# POWER.net
KiCad netlist of a schematic drawn in Altium Designer
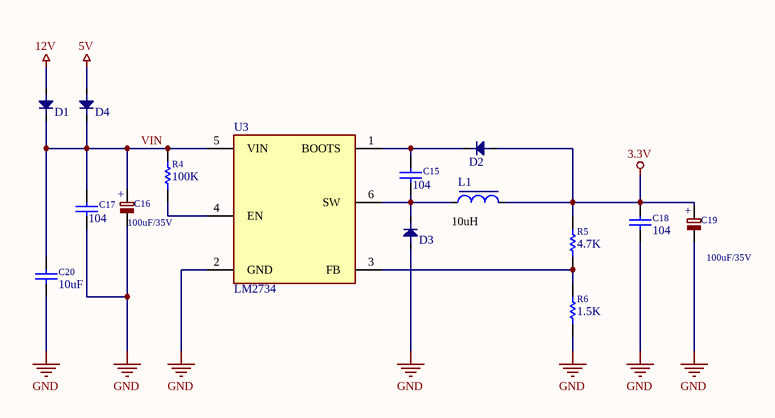
[diagram p0: POWER.SchDoc]

(export (version "E")
  (design (tool "Eeschema 10.0.6"))
  (components
    (comp (ref "C15")
      (value "104")
      (footprint "C2012-0805")
      (description "Capacitor")
      (fields (field (name "PUBLISHER") "Hoang Nguyen"))
      (libsource (lib "VPMyLibrary") (part "Cap {lt}SMD{gt}"))
    )
    (comp (ref "C16")
      (value "100uF/35V")
      (footprint "CAP_100/35V")
      (description "Polarized Capacitor")
      (fields (field (name "MANUFACTURER") "FARNELL") (field (name "PUBLISHER") "Hoang Nguyen"))
      (libsource (lib "VPMyLibrary") (part "Cap_Pol {lt}DIP{gt}"))
    )
    (comp (ref "C17")
      (value "104")
      (footprint "C2012-0805")
      (description "Capacitor")
      (fields (field (name "PUBLISHER") "Hoang Nguyen"))
      (libsource (lib "VPMyLibrary") (part "Cap {lt}SMD{gt}"))
    )
    (comp (ref "C18")
      (value "104")
      (footprint "C2012-0805")
      (description "Capacitor")
      (fields (field (name "PUBLISHER") "Hoang Nguyen"))
      (libsource (lib "VPMyLibrary") (part "Cap {lt}SMD{gt}"))
    )
    (comp (ref "C19")
      (value "100uF/35V")
      (footprint "CAP_100/35V")
      (description "Polarized Capacitor")
      (fields (field (name "MANUFACTURER") "FARNELL") (field (name "PUBLISHER") "Hoang Nguyen"))
      (libsource (lib "VPMyLibrary") (part "Cap_Pol {lt}DIP{gt}"))
    )
    (comp (ref "C20")
      (value "10uF")
      (footprint "C1210")
      (description "Capacitor")
      (fields (field (name "PUBLISHER") "Hoang Nguyen"))
      (libsource (lib "VPMyLibrary") (part "Cap {lt}SMD{gt}"))
    )
    (comp (ref "D1")
      (value "SS34")
      (footprint "DO-214AC,SMA")
      (fields (field (name "PUBLISHER") "Altium Limited"))
      (libsource (lib "VPMyLibrary") (part "Didode_Smd"))
    )
    (comp (ref "D2")
      (value "SS34")
      (footprint "DO-214AC,SMA")
      (fields (field (name "PUBLISHER") "Altium Limited"))
      (libsource (lib "VPMyLibrary") (part "Didode_Smd"))
    )
    (comp (ref "D3")
      (value "SS34")
      (footprint "DO-214AC,SMA")
      (fields (field (name "PUBLISHER") "Altium Limited"))
      (libsource (lib "VPMyLibrary") (part "Didode_Smd"))
    )
    (comp (ref "D4")
      (value "SS34")
      (footprint "DO-214AC,SMA")
      (fields (field (name "PUBLISHER") "Altium Limited"))
      (libsource (lib "VPMyLibrary") (part "Didode_Smd"))
    )
    (comp (ref "L1")
      (value "10uH")
      (footprint "L-6030")
      (description "Smd Inductors")
      (fields (field (name "PUBLISHER") "Altium Limited"))
      (libsource (lib "VPMyLibrary") (part "Inductor Ferrite"))
    )
    (comp (ref "R4")
      (value "100K")
      (footprint "R2012-0805")
      (description "Resistor")
      (fields (field (name "Comment") "4.7K") (field (name "PUBLISHER") "Hoang Nguyen"))
      (libsource (lib "VPMyLibrary") (part "Resistor {lt}SMD{gt}"))
    )
    (comp (ref "R5")
      (value "4.7K")
      (footprint "R2012-0805")
      (description "Resistor")
      (fields (field (name "PUBLISHER") "Hoang Nguyen"))
      (libsource (lib "VPMyLibrary") (part "Resistor {lt}SMD{gt}"))
    )
    (comp (ref "R6")
      (value "1.5K")
      (footprint "R2012-0805")
      (description "Resistor")
      (fields (field (name "PUBLISHER") "Hoang Nguyen"))
      (libsource (lib "VPMyLibrary") (part "Resistor {lt}SMD{gt}"))
    )
    (comp (ref "U3")
      (value "LM2734")
      (footprint "SOT23-6")
      (description "Step-Down DC-DC Regulator")
      (libsource (lib "VPMyLibrary") (part "LM2734"))
    )
  )
  (nets
    (net (code "1") (name "/VIN") (class "Default")
      (node (ref "C16") (pin "1") (pinfunction "+_1") (pintype "passive"))
      (node (ref "C17") (pin "1") (pinfunction "1_1") (pintype "passive"))
      (node (ref "C20") (pin "1") (pinfunction "1_1") (pintype "passive"))
      (node (ref "D1") (pin "2") (pinfunction "K_2") (pintype "passive"))
      (node (ref "D4") (pin "2") (pinfunction "K_2") (pintype "passive"))
      (node (ref "R4") (pin "2") (pinfunction "2_2") (pintype "passive"))
      (node (ref "U3") (pin "5") (pinfunction "VIN_5") (pintype "passive"))
    )
    (net (code "2") (name "3.3V") (class "Default")
      (node (ref "C18") (pin "1") (pinfunction "1_1") (pintype "passive"))
      (node (ref "C19") (pin "1") (pinfunction "+_1") (pintype "passive"))
      (node (ref "D2") (pin "1") (pinfunction "A_1") (pintype "passive"))
      (node (ref "L1") (pin "2") (pinfunction "2_2") (pintype "passive"))
      (node (ref "R5") (pin "2") (pinfunction "2_2") (pintype "passive"))
    )
    (net (code "3") (name "5V") (class "Default")
      (node (ref "D4") (pin "1") (pinfunction "A_1") (pintype "passive"))
    )
    (net (code "4") (name "12V") (class "Default")
      (node (ref "D1") (pin "1") (pinfunction "A_1") (pintype "passive"))
    )
    (net (code "5") (name "GND") (class "Default")
      (node (ref "C16") (pin "2") (pinfunction "-_2") (pintype "passive"))
      (node (ref "C17") (pin "2") (pinfunction "2_2") (pintype "passive"))
      (node (ref "C18") (pin "2") (pinfunction "2_2") (pintype "passive"))
      (node (ref "C19") (pin "2") (pinfunction "-_2") (pintype "passive"))
      (node (ref "C20") (pin "2") (pinfunction "2_2") (pintype "passive"))
      (node (ref "D3") (pin "1") (pinfunction "A_1") (pintype "passive"))
      (node (ref "R6") (pin "1") (pinfunction "1_1") (pintype "passive"))
      (node (ref "U3") (pin "2") (pinfunction "GND_2") (pintype "passive"))
    )
    (net (code "6") (name "Net-(D2-K)") (class "Default")
      (node (ref "C15") (pin "1") (pinfunction "1_1") (pintype "passive"))
      (node (ref "D2") (pin "2") (pinfunction "K_2") (pintype "passive"))
      (node (ref "U3") (pin "1") (pinfunction "BOOTS_1") (pintype "passive"))
    )
    (net (code "7") (name "Net-(D3-K)") (class "Default")
      (node (ref "C15") (pin "2") (pinfunction "2_2") (pintype "passive"))
      (node (ref "D3") (pin "2") (pinfunction "K_2") (pintype "passive"))
      (node (ref "L1") (pin "1") (pinfunction "1_1") (pintype "passive"))
      (node (ref "U3") (pin "6") (pinfunction "SW_6") (pintype "passive"))
    )
    (net (code "8") (name "Net-(U3-EN)") (class "Default")
      (node (ref "R4") (pin "1") (pinfunction "1_1") (pintype "passive"))
      (node (ref "U3") (pin "4") (pinfunction "EN_4") (pintype "passive"))
    )
    (net (code "9") (name "Net-(U3-FB)") (class "Default")
      (node (ref "R5") (pin "1") (pinfunction "1_1") (pintype "passive"))
      (node (ref "R6") (pin "2") (pinfunction "2_2") (pintype "passive"))
      (node (ref "U3") (pin "3") (pinfunction "FB_3") (pintype "passive"))
    )
  )
)
